# IV18InCase.net
KiCad netlist of a schematic drawn in Altium Designer
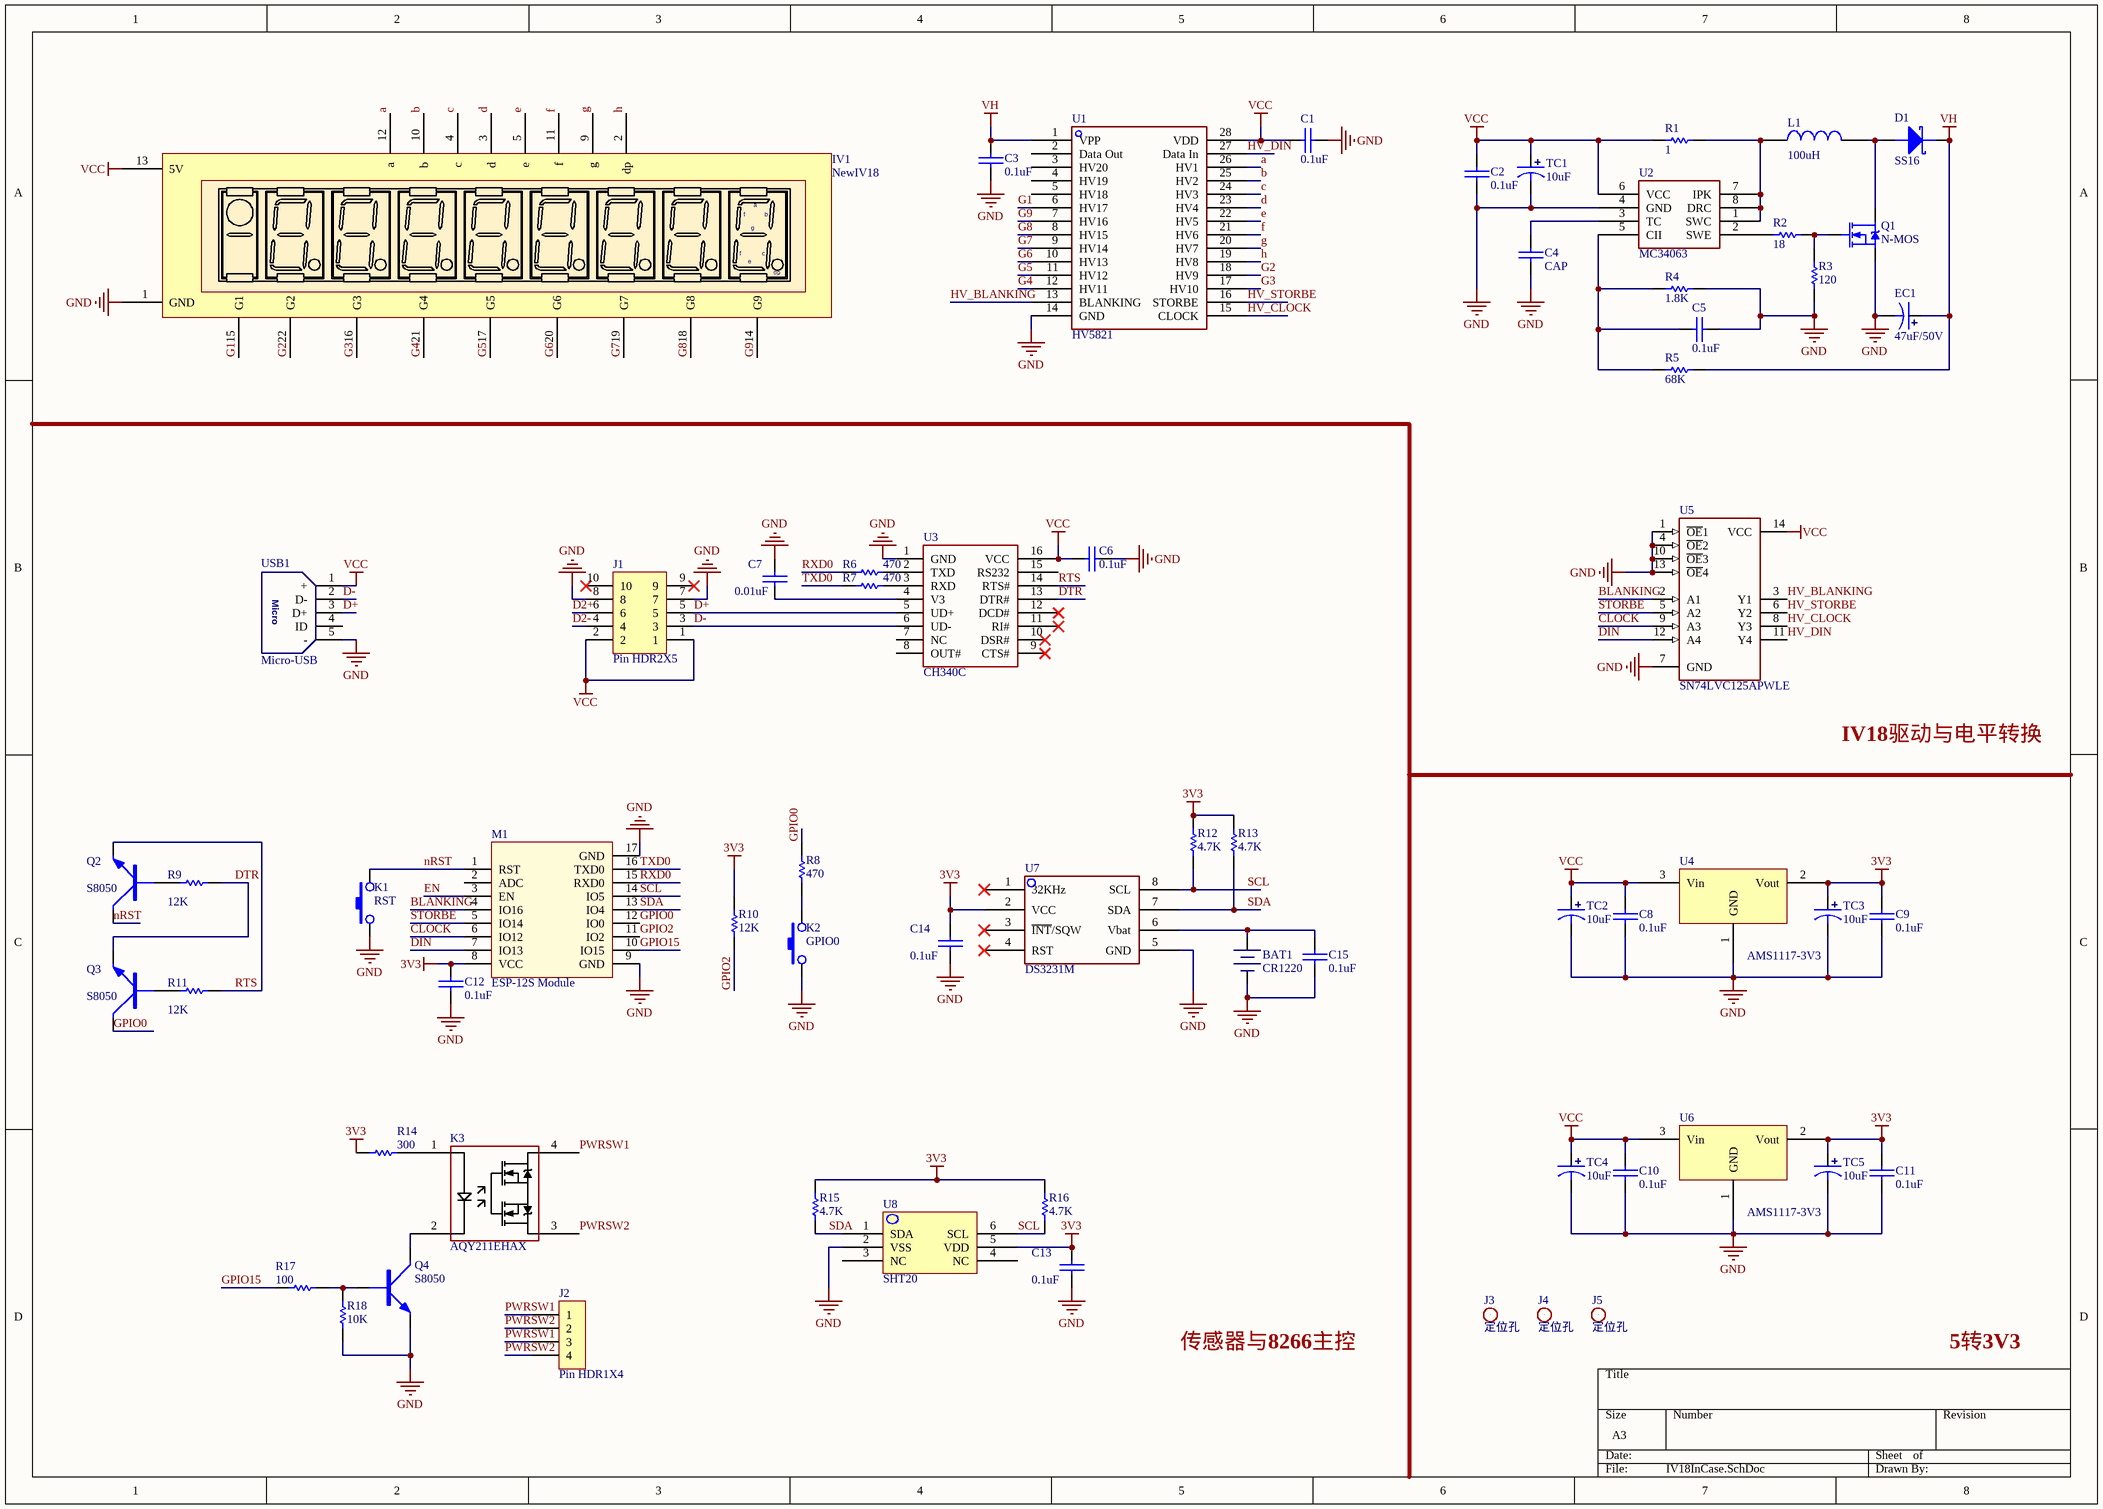
[diagram p0: IV18InCase.SchDoc]

(export (version "E")
  (design (tool "Eeschema 10.0.6"))
  (components
    (comp (ref "BAT1")
      (value "CR1220")
      (footprint "CR1220-B")
      (libsource (lib "altium-import") (part "root_3_CR1220_"))
    )
    (comp (ref "C1")
      (value "0.1uF")
      (footprint "0603C")
      (description "无极性电容")
      (libsource (lib "altium-import") (part "root_2_CAP_"))
    )
    (comp (ref "C2")
      (value "0.1uF")
      (footprint "0603C")
      (description "无极性电容")
      (libsource (lib "altium-import") (part "root_1_CAP_"))
    )
    (comp (ref "C3")
      (value "0.1uF")
      (footprint "0603C")
      (description "无极性电容")
      (libsource (lib "altium-import") (part "root_1_CAP_"))
    )
    (comp (ref "C4")
      (value "CAP")
      (footprint "0603C")
      (description "无极性电容")
      (libsource (lib "altium-import") (part "root_1_CAP_"))
    )
    (comp (ref "C5")
      (value "0.1uF")
      (footprint "0603C")
      (description "无极性电容")
      (libsource (lib "altium-import") (part "root_2_CAP_"))
    )
    (comp (ref "C6")
      (value "0.1uF")
      (footprint "0603C")
      (description "无极性电容")
      (libsource (lib "altium-import") (part "root_2_CAP_"))
    )
    (comp (ref "C7")
      (value "0.01uF")
      (footprint "0603C")
      (description "无极性电容")
      (libsource (lib "altium-import") (part "root_3_CAP_"))
    )
    (comp (ref "C8")
      (value "0.1uF")
      (footprint "0603C")
      (description "无极性电容")
      (libsource (lib "altium-import") (part "root_1_CAP_"))
    )
    (comp (ref "C9")
      (value "0.1uF")
      (footprint "0603C")
      (description "无极性电容")
      (libsource (lib "altium-import") (part "root_1_CAP_"))
    )
    (comp (ref "C10")
      (value "0.1uF")
      (footprint "0603C")
      (description "无极性电容")
      (libsource (lib "altium-import") (part "root_1_CAP_"))
    )
    (comp (ref "C11")
      (value "0.1uF")
      (footprint "0603C")
      (description "无极性电容")
      (libsource (lib "altium-import") (part "root_1_CAP_"))
    )
    (comp (ref "C12")
      (value "0.1uF")
      (footprint "0603C")
      (description "无极性电容")
      (libsource (lib "altium-import") (part "root_1_CAP_"))
    )
    (comp (ref "C13")
      (value "0.1uF")
      (footprint "0603C")
      (description "无极性电容")
      (libsource (lib "altium-import") (part "root_1_CAP_"))
    )
    (comp (ref "C14")
      (value "0.1uF")
      (footprint "0603C")
      (description "无极性电容")
      (libsource (lib "altium-import") (part "root_1_CAP_"))
    )
    (comp (ref "C15")
      (value "0.1uF")
      (footprint "0603C")
      (description "无极性电容")
      (libsource (lib "altium-import") (part "root_1_CAP_"))
    )
    (comp (ref "D1")
      (value "SS16")
      (footprint "SMA/DO-214AC")
      (description "肖特基二极管")
      (libsource (lib "altium-import") (part "root_0_DIODE SCHOTTKY_"))
    )
    (comp (ref "EC1")
      (value "47uF/50V")
      (footprint "SMD-EC3.0X3.3X5.4")
      (description "贴片电解电容")
      (libsource (lib "altium-import") (part "root_2_SMD_ECAP_"))
    )
    (comp (ref "IV1")
      (value "NewIV18")
      (footprint "NEWIV18-正向")
      (libsource (lib "altium-import") (part "root_0_NewIV18_"))
    )
    (comp (ref "J1")
      (value "Pin HDR2X5")
      (footprint "Pin HDR2X5/2.54mm-S")
      (libsource (lib "altium-import") (part "root_1_Pin HDR2X5_"))
    )
    (comp (ref "J2")
      (value "Pin HDR1X4")
      (footprint "Pin HDR1X4/2.54mm-S")
      (libsource (lib "altium-import") (part "root_0_Pin HDR1X4_"))
    )
    (comp (ref "J3") (value "定位孔") (footprint "铜柱定位孔") (libsource (lib "NIXIXH_V2.0") (part "定位孔")))
    (comp (ref "J4") (value "定位孔") (footprint "铜柱定位孔") (libsource (lib "NIXIXH_V2.0") (part "定位孔")))
    (comp (ref "J5") (value "定位孔") (footprint "铜柱定位孔") (libsource (lib "NIXIXH_V2.0") (part "定位孔")))
    (comp (ref "K1")
      (value "RST")
      (footprint "SMD-3X6X2.5")
      (libsource (lib "altium-import") (part "root_1_KEY_"))
    )
    (comp (ref "K2")
      (value "GPIO0")
      (footprint "SMD-3X6X2.5")
      (libsource (lib "altium-import") (part "root_1_KEY_"))
    )
    (comp (ref "K3")
      (value "AQY211EHAX")
      (footprint "SMD4")
      (libsource (lib "NIXIXH_V2.0") (part "AQY211EHAX"))
    )
    (comp (ref "L1")
      (value "100uH")
      (footprint "CD32")
      (description "INDUCTOR")
      (libsource (lib "altium-import") (part "root_0_INDUCTOR_"))
    )
    (comp (ref "M1")
      (value "ESP-12S Module")
      (footprint "ESP-12S Module")
      (libsource (lib "altium-import") (part "root_0_ESP-12S Module_"))
    )
    (comp (ref "Q1")
      (value "N-MOS")
      (footprint "TO252")
      (description "N沟道场效应管")
      (libsource (lib "altium-import") (part "root_0_N-MOS_"))
    )
    (comp (ref "Q2")
      (value "S8050")
      (footprint "SOT-23")
      (description "NPN三极管")
      (libsource (lib "altium-import") (part "root_2_NPN_"))
    )
    (comp (ref "Q3")
      (value "S8050")
      (footprint "SOT-23")
      (description "NPN三极管")
      (libsource (lib "altium-import") (part "root_2_NPN_"))
    )
    (comp (ref "Q4")
      (value "S8050")
      (footprint "SOT-23")
      (description "NPN三极管")
      (libsource (lib "altium-import") (part "root_0_NPN_"))
    )
    (comp (ref "R1") (value "1") (footprint "0603R") (libsource (lib "altium-import") (part "root_0_RES_")))
    (comp (ref "R2") (value "18") (footprint "0603R") (libsource (lib "altium-import") (part "root_0_RES_")))
    (comp (ref "R3") (value "120") (footprint "0603R") (libsource (lib "altium-import") (part "root_1_RES_")))
    (comp (ref "R4")
      (value "1.8K")
      (footprint "0603R")
      (libsource (lib "altium-import") (part "root_0_RES_"))
    )
    (comp (ref "R5") (value "68K") (footprint "0603R") (libsource (lib "altium-import") (part "root_0_RES_")))
    (comp (ref "R6") (value "470") (footprint "0603R") (libsource (lib "altium-import") (part "root_0_RES_")))
    (comp (ref "R7") (value "470") (footprint "0603R") (libsource (lib "altium-import") (part "root_0_RES_")))
    (comp (ref "R8") (value "470") (footprint "0603R") (libsource (lib "altium-import") (part "root_1_RES_")))
    (comp (ref "R9") (value "12K") (footprint "0603R") (libsource (lib "altium-import") (part "root_0_RES_")))
    (comp (ref "R10")
      (value "12K")
      (footprint "0603R")
      (libsource (lib "altium-import") (part "root_1_RES_"))
    )
    (comp (ref "R11")
      (value "12K")
      (footprint "0603R")
      (libsource (lib "altium-import") (part "root_0_RES_"))
    )
    (comp (ref "R12")
      (value "4.7K")
      (footprint "0603R")
      (libsource (lib "altium-import") (part "root_1_RES_"))
    )
    (comp (ref "R13")
      (value "4.7K")
      (footprint "0603R")
      (libsource (lib "altium-import") (part "root_1_RES_"))
    )
    (comp (ref "R14")
      (value "300")
      (footprint "0603R")
      (libsource (lib "altium-import") (part "root_0_RES_"))
    )
    (comp (ref "R15")
      (value "4.7K")
      (footprint "0603R")
      (libsource (lib "altium-import") (part "root_1_RES_"))
    )
    (comp (ref "R16")
      (value "4.7K")
      (footprint "0603R")
      (libsource (lib "altium-import") (part "root_1_RES_"))
    )
    (comp (ref "R17")
      (value "100")
      (footprint "0603R")
      (libsource (lib "altium-import") (part "root_0_RES_"))
    )
    (comp (ref "R18")
      (value "10K")
      (footprint "0603R")
      (libsource (lib "altium-import") (part "root_1_RES_"))
    )
    (comp (ref "TC1")
      (value "10uF")
      (footprint "TAJ-A/3216")
      (description "钽电容")
      (libsource (lib "altium-import") (part "root_3_TCAP_"))
    )
    (comp (ref "TC2")
      (value "10uF")
      (footprint "TAJ-A/3216")
      (description "钽电容")
      (libsource (lib "altium-import") (part "root_3_TCAP_"))
    )
    (comp (ref "TC3")
      (value "10uF")
      (footprint "TAJ-A/3216")
      (description "钽电容")
      (libsource (lib "altium-import") (part "root_3_TCAP_"))
    )
    (comp (ref "TC4")
      (value "10uF")
      (footprint "TAJ-A/3216")
      (description "钽电容")
      (libsource (lib "altium-import") (part "root_3_TCAP_"))
    )
    (comp (ref "TC5")
      (value "10uF")
      (footprint "TAJ-A/3216")
      (description "钽电容")
      (libsource (lib "altium-import") (part "root_3_TCAP_"))
    )
    (comp (ref "U1") (value "HV5821") (footprint "SOIC_28W") (libsource (lib "NIXIXH_V2.0") (part "HV5821")))
    (comp (ref "U2") (value "MC34063") (footprint "SOP8") (libsource (lib "NIXIXH_V2.0") (part "MC34063")))
    (comp (ref "U3") (value "CH340C") (footprint "SOP16") (libsource (lib "NIXIXH_V2.0") (part "CH340C")))
    (comp (ref "U4")
      (value "AMS1117-3V3")
      (footprint "SOT223")
      (description "三端稳压芯片")
      (libsource (lib "altium-import") (part "root_0_AMS1117_"))
    )
    (comp (ref "U5")
      (value "SN74LVC125APWLE")
      (footprint "TSSOP14")
      (libsource (lib "NIXIXH_V2.0") (part "SN74LVC125APWLE"))
    )
    (comp (ref "U6")
      (value "AMS1117-3V3")
      (footprint "SOT223")
      (description "三端稳压芯片")
      (libsource (lib "altium-import") (part "root_0_AMS1117_"))
    )
    (comp (ref "U7") (value "DS3231M") (footprint "SOP8") (libsource (lib "NIXIXH_V2.0") (part "DS3231M")))
    (comp (ref "U8") (value "SHT20") (footprint "SHT-20") (libsource (lib "NIXIXH_V2.0") (part "SHT20")))
    (comp (ref "USB1")
      (value "Micro-USB")
      (footprint "USB-MICRO_A")
      (libsource (lib "altium-import") (part "root_0_Micro-USB_"))
    )
  )
  (nets
    (net (code "1") (name "/BLANKING") (class "Default")
      (node (ref "M1") (pin "4") (pinfunction "IO16_4") (pintype "passive"))
      (node (ref "U5") (pin "2") (pinfunction "A1_2") (pintype "input"))
    )
    (net (code "2") (name "/CLOCK") (class "Default")
      (node (ref "M1") (pin "6") (pinfunction "IO12_6") (pintype "passive"))
      (node (ref "U5") (pin "9") (pinfunction "A3_9") (pintype "input"))
    )
    (net (code "3") (name "/D+") (class "Default")
      (node (ref "J1") (pin "5") (pinfunction "5_5") (pintype "passive"))
      (node (ref "U3") (pin "5") (pinfunction "UD+_5") (pintype "passive"))
      (node (ref "USB1") (pin "3") (pinfunction "D+_3") (pintype "passive"))
    )
    (net (code "4") (name "/D-") (class "Default")
      (node (ref "J1") (pin "3") (pinfunction "3_3") (pintype "passive"))
      (node (ref "U3") (pin "6") (pinfunction "UD-_6") (pintype "passive"))
      (node (ref "USB1") (pin "2") (pinfunction "D-_2") (pintype "passive"))
    )
    (net (code "5") (name "/D2+") (class "Default")
      (node (ref "J1") (pin "6") (pinfunction "6_6") (pintype "passive"))
    )
    (net (code "6") (name "/D2-") (class "Default")
      (node (ref "J1") (pin "4") (pinfunction "4_4") (pintype "passive"))
    )
    (net (code "7") (name "/DIN") (class "Default")
      (node (ref "M1") (pin "7") (pinfunction "IO13_7") (pintype "passive"))
      (node (ref "U5") (pin "12") (pinfunction "A4_12") (pintype "input"))
    )
    (net (code "8") (name "/DTR") (class "Default")
      (node (ref "Q3") (pin "E") (pinfunction "E_E") (pintype "passive"))
      (node (ref "R9") (pin "2") (pinfunction "2_2") (pintype "passive"))
      (node (ref "U3") (pin "13") (pinfunction "DTR#_13") (pintype "passive"))
    )
    (net (code "9") (name "/EN") (class "Default")
      (node (ref "M1") (pin "3") (pinfunction "EN_3") (pintype "passive"))
    )
    (net (code "10") (name "/G1") (class "Default")
      (node (ref "IV1") (pin "15") (pinfunction "G1_15") (pintype "passive"))
      (node (ref "U1") (pin "6") (pinfunction "HV17_6") (pintype "passive"))
    )
    (net (code "11") (name "/G2") (class "Default")
      (node (ref "IV1") (pin "22") (pinfunction "G2_22") (pintype "passive"))
      (node (ref "U1") (pin "18") (pinfunction "HV9_18") (pintype "passive"))
    )
    (net (code "12") (name "/G3") (class "Default")
      (node (ref "IV1") (pin "16") (pinfunction "G3_16") (pintype "passive"))
      (node (ref "U1") (pin "17") (pinfunction "HV10_17") (pintype "passive"))
    )
    (net (code "13") (name "/G4") (class "Default")
      (node (ref "IV1") (pin "21") (pinfunction "G4_21") (pintype "passive"))
      (node (ref "U1") (pin "12") (pinfunction "HV11_12") (pintype "passive"))
    )
    (net (code "14") (name "/G5") (class "Default")
      (node (ref "IV1") (pin "17") (pinfunction "G5_17") (pintype "passive"))
      (node (ref "U1") (pin "11") (pinfunction "HV12_11") (pintype "passive"))
    )
    (net (code "15") (name "/G6") (class "Default")
      (node (ref "IV1") (pin "20") (pinfunction "G6_20") (pintype "passive"))
      (node (ref "U1") (pin "10") (pinfunction "HV13_10") (pintype "passive"))
    )
    (net (code "16") (name "/G7") (class "Default")
      (node (ref "IV1") (pin "19") (pinfunction "G7_19") (pintype "passive"))
      (node (ref "U1") (pin "9") (pinfunction "HV14_9") (pintype "passive"))
    )
    (net (code "17") (name "/G8") (class "Default")
      (node (ref "IV1") (pin "18") (pinfunction "G8_18") (pintype "passive"))
      (node (ref "U1") (pin "8") (pinfunction "HV15_8") (pintype "passive"))
    )
    (net (code "18") (name "/G9") (class "Default")
      (node (ref "IV1") (pin "14") (pinfunction "G9_14") (pintype "passive"))
      (node (ref "U1") (pin "7") (pinfunction "HV16_7") (pintype "passive"))
    )
    (net (code "19") (name "/GPIO0") (class "Default")
      (node (ref "M1") (pin "12") (pinfunction "IO0_12") (pintype "passive"))
      (node (ref "Q3") (pin "C") (pinfunction "C_C") (pintype "passive"))
      (node (ref "R8") (pin "2") (pinfunction "2_2") (pintype "passive"))
    )
    (net (code "20") (name "/GPIO2") (class "Default")
      (node (ref "M1") (pin "11") (pinfunction "IO2_11") (pintype "passive"))
      (node (ref "R10") (pin "1") (pinfunction "1_1") (pintype "passive"))
    )
    (net (code "21") (name "/GPIO15") (class "Default")
      (node (ref "M1") (pin "10") (pinfunction "IO15_10") (pintype "passive"))
      (node (ref "R17") (pin "1") (pinfunction "1_1") (pintype "passive"))
    )
    (net (code "22") (name "/HV_BLANKING") (class "Default")
      (node (ref "U1") (pin "13") (pinfunction "BLANKING_13") (pintype "passive"))
      (node (ref "U5") (pin "3") (pinfunction "Y1_3") (pintype "tri_state"))
    )
    (net (code "23") (name "/HV_CLOCK") (class "Default")
      (node (ref "U1") (pin "15") (pinfunction "CLOCK_15") (pintype "passive"))
      (node (ref "U5") (pin "8") (pinfunction "Y3_8") (pintype "tri_state"))
    )
    (net (code "24") (name "/HV_DIN") (class "Default")
      (node (ref "U1") (pin "27") (pinfunction "Data_In_27") (pintype "passive"))
      (node (ref "U5") (pin "11") (pinfunction "Y4_11") (pintype "tri_state"))
    )
    (net (code "25") (name "/HV_STORBE") (class "Default")
      (node (ref "U1") (pin "16") (pinfunction "STORBE_16") (pintype "passive"))
      (node (ref "U5") (pin "6") (pinfunction "Y2_6") (pintype "tri_state"))
    )
    (net (code "26") (name "/PWRSW1") (class "Default")
      (node (ref "J2") (pin "1") (pinfunction "1_1") (pintype "passive"))
      (node (ref "J2") (pin "3") (pinfunction "3_3") (pintype "passive"))
      (node (ref "K3") (pin "4") (pinfunction "4_4") (pintype "passive"))
    )
    (net (code "27") (name "/PWRSW2") (class "Default")
      (node (ref "J2") (pin "2") (pinfunction "2_2") (pintype "passive"))
      (node (ref "J2") (pin "4") (pinfunction "4_4") (pintype "passive"))
      (node (ref "K3") (pin "3") (pinfunction "3_3") (pintype "passive"))
    )
    (net (code "28") (name "/RTS") (class "Default")
      (node (ref "Q2") (pin "E") (pinfunction "E_E") (pintype "passive"))
      (node (ref "R11") (pin "2") (pinfunction "2_2") (pintype "passive"))
      (node (ref "U3") (pin "14") (pinfunction "RTS#_14") (pintype "passive"))
    )
    (net (code "29") (name "/RXD0") (class "Default")
      (node (ref "M1") (pin "15") (pinfunction "RXD0_15") (pintype "passive"))
      (node (ref "R6") (pin "1") (pinfunction "1_1") (pintype "passive"))
    )
    (net (code "30") (name "/SCL") (class "Default")
      (node (ref "M1") (pin "14") (pinfunction "IO5_14") (pintype "passive"))
      (node (ref "R12") (pin "1") (pinfunction "1_1") (pintype "passive"))
      (node (ref "R16") (pin "1") (pinfunction "1_1") (pintype "passive"))
      (node (ref "U7") (pin "8") (pinfunction "SCL_8") (pintype "passive"))
      (node (ref "U8") (pin "6") (pinfunction "SCL_6") (pintype "passive"))
    )
    (net (code "31") (name "/SDA") (class "Default")
      (node (ref "M1") (pin "13") (pinfunction "IO4_13") (pintype "passive"))
      (node (ref "R13") (pin "1") (pinfunction "1_1") (pintype "passive"))
      (node (ref "R15") (pin "1") (pinfunction "1_1") (pintype "passive"))
      (node (ref "U7") (pin "7") (pinfunction "SDA_7") (pintype "passive"))
      (node (ref "U8") (pin "1") (pinfunction "SDA_1") (pintype "passive"))
    )
    (net (code "32") (name "/STORBE") (class "Default")
      (node (ref "M1") (pin "5") (pinfunction "IO14_5") (pintype "passive"))
      (node (ref "U5") (pin "5") (pinfunction "A2_5") (pintype "input"))
    )
    (net (code "33") (name "/TXD0") (class "Default")
      (node (ref "M1") (pin "16") (pinfunction "TXD0_16") (pintype "passive"))
      (node (ref "R7") (pin "1") (pinfunction "1_1") (pintype "passive"))
    )
    (net (code "34") (name "/a") (class "Default")
      (node (ref "IV1") (pin "12") (pinfunction "a_12") (pintype "passive"))
      (node (ref "U1") (pin "26") (pinfunction "HV1_26") (pintype "passive"))
    )
    (net (code "35") (name "/b") (class "Default")
      (node (ref "IV1") (pin "10") (pinfunction "b_10") (pintype "passive"))
      (node (ref "U1") (pin "25") (pinfunction "HV2_25") (pintype "passive"))
    )
    (net (code "36") (name "/c") (class "Default")
      (node (ref "IV1") (pin "4") (pinfunction "c_4") (pintype "passive"))
      (node (ref "U1") (pin "24") (pinfunction "HV3_24") (pintype "passive"))
    )
    (net (code "37") (name "/d") (class "Default")
      (node (ref "IV1") (pin "3") (pinfunction "d_3") (pintype "passive"))
      (node (ref "U1") (pin "23") (pinfunction "HV4_23") (pintype "passive"))
    )
    (net (code "38") (name "/e") (class "Default")
      (node (ref "IV1") (pin "5") (pinfunction "e_5") (pintype "passive"))
      (node (ref "U1") (pin "22") (pinfunction "HV5_22") (pintype "passive"))
    )
    (net (code "39") (name "/f") (class "Default")
      (node (ref "IV1") (pin "11") (pinfunction "f_11") (pintype "passive"))
      (node (ref "U1") (pin "21") (pinfunction "HV6_21") (pintype "passive"))
    )
    (net (code "40") (name "/g") (class "Default")
      (node (ref "IV1") (pin "9") (pinfunction "g_9") (pintype "passive"))
      (node (ref "U1") (pin "20") (pinfunction "HV7_20") (pintype "passive"))
    )
    (net (code "41") (name "/h") (class "Default")
      (node (ref "IV1") (pin "2") (pinfunction "dp_2") (pintype "passive"))
      (node (ref "U1") (pin "19") (pinfunction "HV8_19") (pintype "passive"))
    )
    (net (code "42") (name "/nRST") (class "Default")
      (node (ref "K1") (pin "3") (pinfunction "3_3") (pintype "passive"))
      (node (ref "M1") (pin "1") (pinfunction "RST_1") (pintype "passive"))
      (node (ref "Q2") (pin "C") (pinfunction "C_C") (pintype "passive"))
    )
    (net (code "43") (name "3V3") (class "Default")
      (node (ref "C11") (pin "2") (pinfunction "2_2") (pintype "passive"))
      (node (ref "C12") (pin "2") (pinfunction "2_2") (pintype "passive"))
      (node (ref "C13") (pin "2") (pinfunction "2_2") (pintype "passive"))
      (node (ref "C14") (pin "2") (pinfunction "2_2") (pintype "passive"))
      (node (ref "C9") (pin "2") (pinfunction "2_2") (pintype "passive"))
      (node (ref "M1") (pin "8") (pinfunction "VCC_8") (pintype "passive"))
      (node (ref "R10") (pin "2") (pinfunction "2_2") (pintype "passive"))
      (node (ref "R12") (pin "2") (pinfunction "2_2") (pintype "passive"))
      (node (ref "R13") (pin "2") (pinfunction "2_2") (pintype "passive"))
      (node (ref "R14") (pin "1") (pinfunction "1_1") (pintype "passive"))
      (node (ref "R15") (pin "2") (pinfunction "2_2") (pintype "passive"))
      (node (ref "R16") (pin "2") (pinfunction "2_2") (pintype "passive"))
      (node (ref "TC3") (pin "1") (pinfunction "1_1") (pintype "passive"))
      (node (ref "TC5") (pin "1") (pinfunction "1_1") (pintype "passive"))
      (node (ref "U4") (pin "2") (pinfunction "Vout_2") (pintype "passive"))
      (node (ref "U6") (pin "2") (pinfunction "Vout_2") (pintype "passive"))
      (node (ref "U7") (pin "2") (pinfunction "VCC_2") (pintype "passive"))
      (node (ref "U8") (pin "5") (pinfunction "VDD_5") (pintype "passive"))
    )
    (net (code "44") (name "GND") (class "Default")
      (node (ref "BAT1") (pin "2") (pinfunction "2_2") (pintype "passive"))
      (node (ref "C1") (pin "1") (pinfunction "1_1") (pintype "passive"))
      (node (ref "C10") (pin "1") (pinfunction "1_1") (pintype "passive"))
      (node (ref "C11") (pin "1") (pinfunction "1_1") (pintype "passive"))
      (node (ref "C12") (pin "1") (pinfunction "1_1") (pintype "passive"))
      (node (ref "C13") (pin "1") (pinfunction "1_1") (pintype "passive"))
      (node (ref "C14") (pin "1") (pinfunction "1_1") (pintype "passive"))
      (node (ref "C15") (pin "1") (pinfunction "1_1") (pintype "passive"))
      (node (ref "C2") (pin "1") (pinfunction "1_1") (pintype "passive"))
      (node (ref "C3") (pin "1") (pinfunction "1_1") (pintype "passive"))
      (node (ref "C4") (pin "1") (pinfunction "1_1") (pintype "passive"))
      (node (ref "C5") (pin "1") (pinfunction "1_1") (pintype "passive"))
      (node (ref "C6") (pin "1") (pinfunction "1_1") (pintype "passive"))
      (node (ref "C7") (pin "1") (pinfunction "1_1") (pintype "passive"))
      (node (ref "C8") (pin "1") (pinfunction "1_1") (pintype "passive"))
      (node (ref "C9") (pin "1") (pinfunction "1_1") (pintype "passive"))
      (node (ref "EC1") (pin "2") (pinfunction "2_2") (pintype "passive"))
      (node (ref "IV1") (pin "1") (pinfunction "GND_1") (pintype "passive"))
      (node (ref "J1") (pin "7") (pinfunction "7_7") (pintype "passive"))
      (node (ref "J1") (pin "8") (pinfunction "8_8") (pintype "passive"))
      (node (ref "K1") (pin "1") (pinfunction "1_1") (pintype "passive"))
      (node (ref "K2") (pin "1") (pinfunction "1_1") (pintype "passive"))
      (node (ref "M1") (pin "17") (pinfunction "GND_17") (pintype "passive"))
      (node (ref "M1") (pin "9") (pinfunction "GND_9") (pintype "passive"))
      (node (ref "Q1") (pin "S") (pinfunction "S_S") (pintype "passive"))
      (node (ref "Q4") (pin "E") (pinfunction "E_E") (pintype "passive"))
      (node (ref "R18") (pin "1") (pinfunction "1_1") (pintype "passive"))
      (node (ref "R3") (pin "1") (pinfunction "1_1") (pintype "passive"))
      (node (ref "R4") (pin "2") (pinfunction "2_2") (pintype "passive"))
      (node (ref "TC1") (pin "2") (pinfunction "2_2") (pintype "passive"))
      (node (ref "TC2") (pin "2") (pinfunction "2_2") (pintype "passive"))
      (node (ref "TC3") (pin "2") (pinfunction "2_2") (pintype "passive"))
      (node (ref "TC4") (pin "2") (pinfunction "2_2") (pintype "passive"))
      (node (ref "TC5") (pin "2") (pinfunction "2_2") (pintype "passive"))
      (node (ref "U1") (pin "14") (pinfunction "GND_14") (pintype "passive"))
      (node (ref "U2") (pin "4") (pinfunction "GND_4") (pintype "passive"))
      (node (ref "U3") (pin "1") (pinfunction "GND_1") (pintype "passive"))
      (node (ref "U4") (pin "1") (pinfunction "GND_1") (pintype "passive"))
      (node (ref "U5") (pin "1") (pinfunction "~{OE}1_1") (pintype "input"))
      (node (ref "U5") (pin "10") (pinfunction "~{OE}3_10") (pintype "input"))
      (node (ref "U5") (pin "13") (pinfunction "~{OE}4_13") (pintype "input"))
      (node (ref "U5") (pin "4") (pinfunction "~{OE}2_4") (pintype "input"))
      (node (ref "U5") (pin "7") (pinfunction "GND_7") (pintype "power_in"))
      (node (ref "U6") (pin "1") (pinfunction "GND_1") (pintype "passive"))
      (node (ref "U7") (pin "5") (pinfunction "GND_5") (pintype "passive"))
      (node (ref "U8") (pin "2") (pinfunction "VSS_2") (pintype "passive"))
      (node (ref "USB1") (pin "5") (pinfunction "-_5") (pintype "passive"))
    )
    (net (code "45") (name "Net-(D1-PadA)") (class "Default")
      (node (ref "D1") (pin "A") (pinfunction "A_A") (pintype "passive"))
      (node (ref "L1") (pin "2") (pinfunction "2_2") (pintype "passive"))
      (node (ref "Q1") (pin "D") (pinfunction "D_D") (pintype "passive"))
    )
    (net (code "46") (name "Net-(K2-Pad3)") (class "Default")
      (node (ref "K2") (pin "3") (pinfunction "3_3") (pintype "passive"))
      (node (ref "R8") (pin "1") (pinfunction "1_1") (pintype "passive"))
    )
    (net (code "47") (name "Net-(K3-Pad1)") (class "Default")
      (node (ref "K3") (pin "1") (pinfunction "1_1") (pintype "passive"))
      (node (ref "R14") (pin "2") (pinfunction "2_2") (pintype "passive"))
    )
    (net (code "48") (name "Net-(K3-Pad2)") (class "Default")
      (node (ref "K3") (pin "2") (pinfunction "2_2") (pintype "passive"))
      (node (ref "Q4") (pin "C") (pinfunction "C_C") (pintype "passive"))
    )
    (net (code "49") (name "Net-(Q1-PadG)") (class "Default")
      (node (ref "Q1") (pin "G") (pinfunction "G_G") (pintype "passive"))
      (node (ref "R2") (pin "2") (pinfunction "2_2") (pintype "passive"))
      (node (ref "R3") (pin "2") (pinfunction "2_2") (pintype "passive"))
    )
    (net (code "50") (name "Net-(Q2-PadB)") (class "Default")
      (node (ref "Q2") (pin "B") (pinfunction "B_B") (pintype "passive"))
      (node (ref "R9") (pin "1") (pinfunction "1_1") (pintype "passive"))
    )
    (net (code "51") (name "Net-(Q3-PadB)") (class "Default")
      (node (ref "Q3") (pin "B") (pinfunction "B_B") (pintype "passive"))
      (node (ref "R11") (pin "1") (pinfunction "1_1") (pintype "passive"))
    )
    (net (code "52") (name "Net-(Q4-PadB)") (class "Default")
      (node (ref "Q4") (pin "B") (pinfunction "B_B") (pintype "passive"))
      (node (ref "R17") (pin "2") (pinfunction "2_2") (pintype "passive"))
      (node (ref "R18") (pin "2") (pinfunction "2_2") (pintype "passive"))
    )
    (net (code "53") (name "Net-(U2-CII)") (class "Default")
      (node (ref "C5") (pin "2") (pinfunction "2_2") (pintype "passive"))
      (node (ref "R4") (pin "1") (pinfunction "1_1") (pintype "passive"))
      (node (ref "R5") (pin "1") (pinfunction "1_1") (pintype "passive"))
      (node (ref "U2") (pin "5") (pinfunction "CII_5") (pintype "passive"))
    )
    (net (code "54") (name "Net-(U2-DRC)") (class "Default")
      (node (ref "L1") (pin "1") (pinfunction "1_1") (pintype "passive"))
      (node (ref "R1") (pin "2") (pinfunction "2_2") (pintype "passive"))
      (node (ref "U2") (pin "1") (pinfunction "SWC_1") (pintype "passive"))
      (node (ref "U2") (pin "7") (pinfunction "IPK_7") (pintype "passive"))
      (node (ref "U2") (pin "8") (pinfunction "DRC_8") (pintype "passive"))
    )
    (net (code "55") (name "Net-(U2-SWE)") (class "Default")
      (node (ref "R2") (pin "1") (pinfunction "1_1") (pintype "passive"))
      (node (ref "U2") (pin "2") (pinfunction "SWE_2") (pintype "passive"))
    )
    (net (code "56") (name "Net-(U2-TC)") (class "Default")
      (node (ref "C4") (pin "2") (pinfunction "2_2") (pintype "passive"))
      (node (ref "U2") (pin "3") (pinfunction "TC_3") (pintype "passive"))
    )
    (net (code "57") (name "Net-(U3-RXD)") (class "Default")
      (node (ref "R7") (pin "2") (pinfunction "2_2") (pintype "passive"))
      (node (ref "U3") (pin "3") (pinfunction "RXD_3") (pintype "passive"))
    )
    (net (code "58") (name "Net-(U3-TXD)") (class "Default")
      (node (ref "R6") (pin "2") (pinfunction "2_2") (pintype "passive"))
      (node (ref "U3") (pin "2") (pinfunction "TXD_2") (pintype "passive"))
    )
    (net (code "59") (name "Net-(U3-V3)") (class "Default")
      (node (ref "C7") (pin "2") (pinfunction "2_2") (pintype "passive"))
      (node (ref "U3") (pin "4") (pinfunction "V3_4") (pintype "passive"))
    )
    (net (code "60") (name "Net-(U7-Vbat)") (class "Default")
      (node (ref "BAT1") (pin "1") (pinfunction "1_1") (pintype "passive"))
      (node (ref "C15") (pin "2") (pinfunction "2_2") (pintype "passive"))
      (node (ref "U7") (pin "6") (pinfunction "Vbat_6") (pintype "passive"))
    )
    (net (code "61") (name "VCC") (class "Default")
      (node (ref "C1") (pin "2") (pinfunction "2_2") (pintype "passive"))
      (node (ref "C10") (pin "2") (pinfunction "2_2") (pintype "passive"))
      (node (ref "C2") (pin "2") (pinfunction "2_2") (pintype "passive"))
      (node (ref "C6") (pin "2") (pinfunction "2_2") (pintype "passive"))
      (node (ref "C8") (pin "2") (pinfunction "2_2") (pintype "passive"))
      (node (ref "IV1") (pin "13") (pinfunction "5V_13") (pintype "passive"))
      (node (ref "J1") (pin "1") (pinfunction "1_1") (pintype "passive"))
      (node (ref "J1") (pin "2") (pinfunction "2_2") (pintype "passive"))
      (node (ref "R1") (pin "1") (pinfunction "1_1") (pintype "passive"))
      (node (ref "TC1") (pin "1") (pinfunction "1_1") (pintype "passive"))
      (node (ref "TC2") (pin "1") (pinfunction "1_1") (pintype "passive"))
      (node (ref "TC4") (pin "1") (pinfunction "1_1") (pintype "passive"))
      (node (ref "U1") (pin "28") (pinfunction "VDD_28") (pintype "passive"))
      (node (ref "U2") (pin "6") (pinfunction "VCC_6") (pintype "passive"))
      (node (ref "U3") (pin "16") (pinfunction "VCC_16") (pintype "passive"))
      (node (ref "U4") (pin "3") (pinfunction "Vin_3") (pintype "passive"))
      (node (ref "U5") (pin "14") (pinfunction "VCC_14") (pintype "power_in"))
      (node (ref "U6") (pin "3") (pinfunction "Vin_3") (pintype "passive"))
      (node (ref "USB1") (pin "1") (pinfunction "+_1") (pintype "passive"))
    )
    (net (code "62") (name "VH") (class "Default")
      (node (ref "C3") (pin "2") (pinfunction "2_2") (pintype "passive"))
      (node (ref "D1") (pin "K") (pinfunction "K_K") (pintype "passive"))
      (node (ref "EC1") (pin "1") (pinfunction "1_1") (pintype "passive"))
      (node (ref "R5") (pin "2") (pinfunction "2_2") (pintype "passive"))
      (node (ref "U1") (pin "1") (pinfunction "VPP_1") (pintype "passive"))
    )
    (net (code "63") (name "unconnected-(J1-Pad9)") (class "Default")
      (node (ref "J1") (pin "9") (pinfunction "9_9") (pintype "passive+no_connect"))
    )
    (net (code "64") (name "unconnected-(J1-Pad10)") (class "Default")
      (node (ref "J1") (pin "10") (pinfunction "10_10") (pintype "passive+no_connect"))
    )
    (net (code "65") (name "unconnected-(J3-Pad1)") (class "Default")
      (node (ref "J3") (pin "1") (pinfunction "1_1") (pintype "passive"))
    )
    (net (code "66") (name "unconnected-(J4-Pad1)") (class "Default")
      (node (ref "J4") (pin "1") (pinfunction "1_1") (pintype "passive"))
    )
    (net (code "67") (name "unconnected-(J5-Pad1)") (class "Default")
      (node (ref "J5") (pin "1") (pinfunction "1_1") (pintype "passive"))
    )
    (net (code "68") (name "unconnected-(M1-ADC-Pad2)") (class "Default")
      (node (ref "M1") (pin "2") (pinfunction "ADC_2") (pintype "passive"))
    )
    (net (code "69") (name "unconnected-(U1-Data_Out-Pad2)") (class "Default")
      (node (ref "U1") (pin "2") (pinfunction "Data_Out_2") (pintype "passive"))
    )
    (net (code "70") (name "unconnected-(U1-HV18-Pad5)") (class "Default")
      (node (ref "U1") (pin "5") (pinfunction "HV18_5") (pintype "passive"))
    )
    (net (code "71") (name "unconnected-(U1-HV19-Pad4)") (class "Default")
      (node (ref "U1") (pin "4") (pinfunction "HV19_4") (pintype "passive"))
    )
    (net (code "72") (name "unconnected-(U1-HV20-Pad3)") (class "Default")
      (node (ref "U1") (pin "3") (pinfunction "HV20_3") (pintype "passive"))
    )
    (net (code "73") (name "unconnected-(U3-CTS#-Pad9)") (class "Default")
      (node (ref "U3") (pin "9") (pinfunction "CTS#_9") (pintype "passive+no_connect"))
    )
    (net (code "74") (name "unconnected-(U3-DCD#-Pad12)") (class "Default")
      (node (ref "U3") (pin "12") (pinfunction "DCD#_12") (pintype "passive+no_connect"))
    )
    (net (code "75") (name "unconnected-(U3-DSR#-Pad10)") (class "Default")
      (node (ref "U3") (pin "10") (pinfunction "DSR#_10") (pintype "passive+no_connect"))
    )
    (net (code "76") (name "unconnected-(U3-NC-Pad7)") (class "Default")
      (node (ref "U3") (pin "7") (pinfunction "NC_7") (pintype "passive"))
    )
    (net (code "77") (name "unconnected-(U3-OUT#-Pad8)") (class "Default")
      (node (ref "U3") (pin "8") (pinfunction "OUT#_8") (pintype "passive"))
    )
    (net (code "78") (name "unconnected-(U3-RI#-Pad11)") (class "Default")
      (node (ref "U3") (pin "11") (pinfunction "RI#_11") (pintype "passive+no_connect"))
    )
    (net (code "79") (name "unconnected-(U3-RS232-Pad15)") (class "Default")
      (node (ref "U3") (pin "15") (pinfunction "RS232_15") (pintype "passive"))
    )
    (net (code "80") (name "unconnected-(U7-32KHz-Pad1)") (class "Default")
      (node (ref "U7") (pin "1") (pinfunction "32KHz_1") (pintype "passive+no_connect"))
    )
    (net (code "81") (name "unconnected-(U7-RST-Pad4)") (class "Default")
      (node (ref "U7") (pin "4") (pinfunction "RST_4") (pintype "passive+no_connect"))
    )
    (net (code "82") (name "unconnected-(U7-~{INT}{slash}SQW-Pad3)") (class "Default")
      (node (ref "U7") (pin "3") (pinfunction "~{INT}/SQW_3") (pintype "passive+no_connect"))
    )
    (net (code "83") (name "unconnected-(U8-NC-Pad3)") (class "Default")
      (node (ref "U8") (pin "3") (pinfunction "NC_3") (pintype "passive"))
    )
    (net (code "84") (name "unconnected-(U8-NC-Pad4)") (class "Default")
      (node (ref "U8") (pin "4") (pinfunction "NC_4") (pintype "passive"))
    )
    (net (code "85") (name "unconnected-(USB1-ID-Pad4)") (class "Default")
      (node (ref "USB1") (pin "4") (pinfunction "ID_4") (pintype "passive"))
    )
  )
)
